# 02_CPU_1214C_DC_DC_DC.net
KiCad netlist of a schematic drawn in Altium Designer
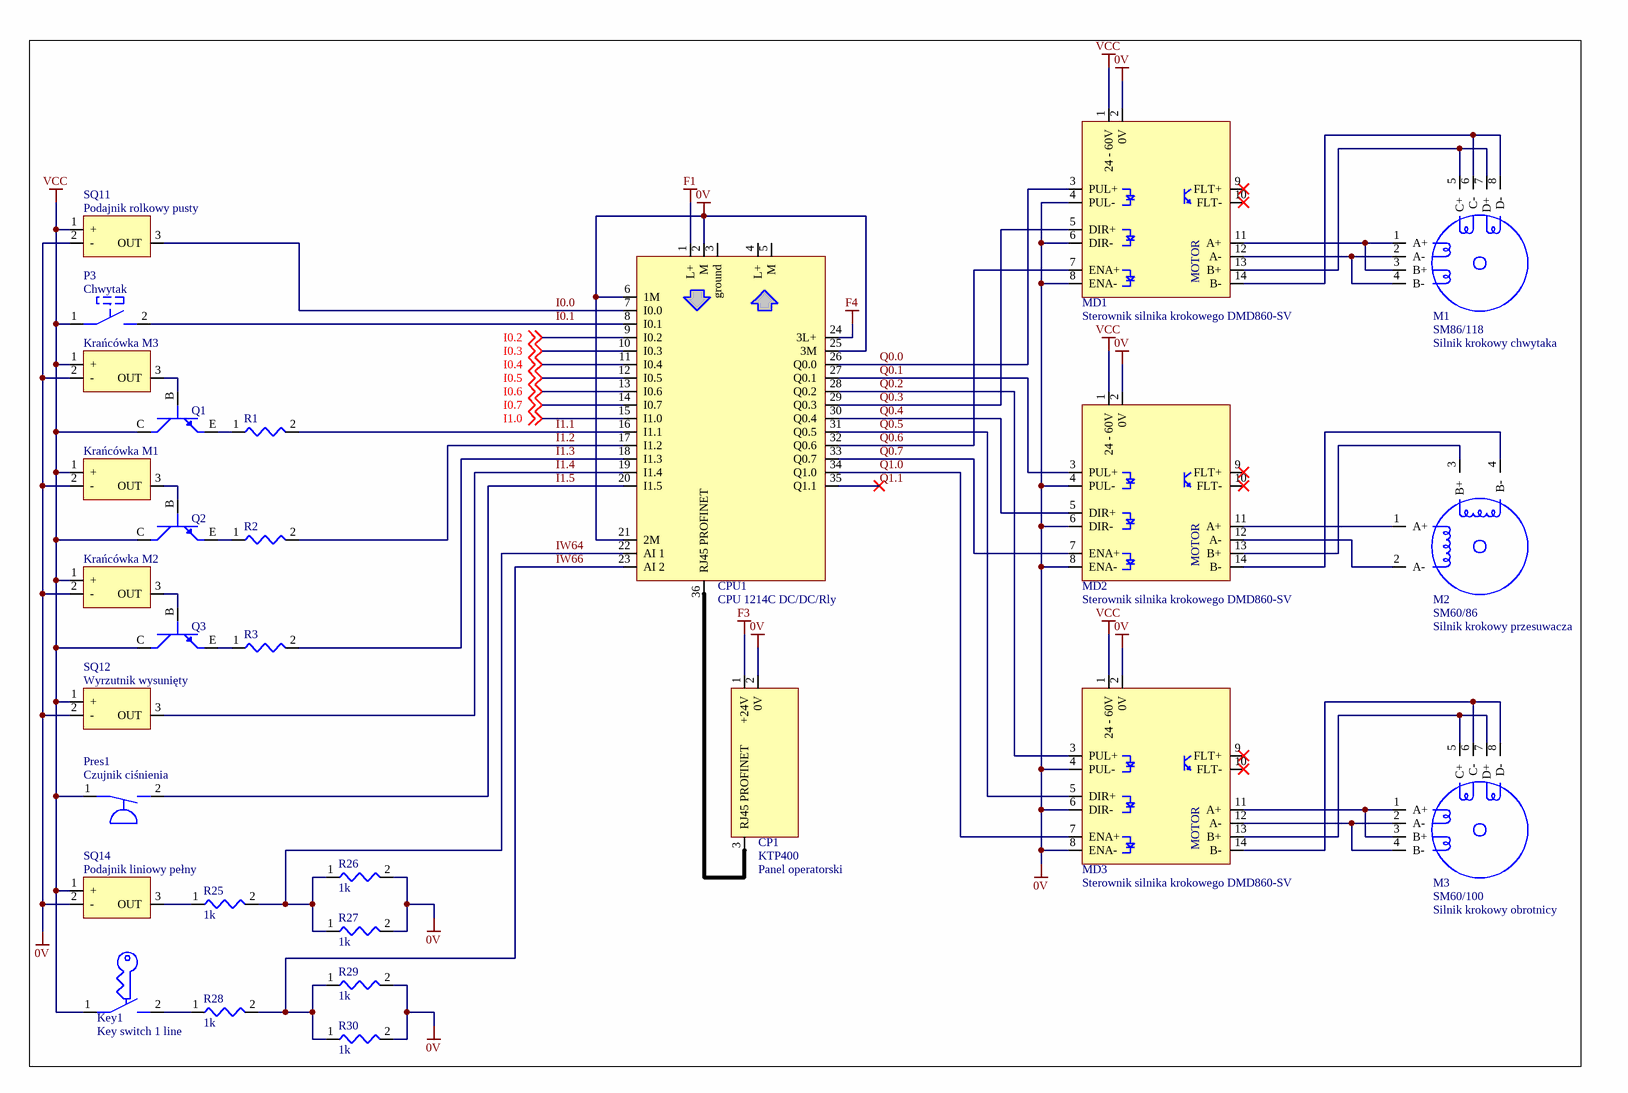
[diagram p0: [02] CPU 1214C DC_DC_DC.SchDoc]

(export (version "E")
  (design (tool "Eeschema 10.0.6"))
  (components
    (comp (ref "CP1") (value "KTP400") (libsource (lib "Schlib1") (part "KTP 400 Basic")))
    (comp (ref "CPU1") (value "CPU 1214C DC/DC/Rly") (libsource (lib "Schlib1") (part "CPU 1214C DC/DC/DC")))
    (comp (ref "Key1") (value "Key switch 1 line") (libsource (lib "Schlib1") (part "Key switch 1 line")))
    (comp (ref "LM1") (value "Krańcówka M1") (libsource (lib "Schlib1") (part "Sensor PNP")))
    (comp (ref "LM2") (value "Krańcówka M2") (libsource (lib "Schlib1") (part "Sensor PNP")))
    (comp (ref "LM3") (value "Krańcówka M3") (libsource (lib "Schlib1") (part "Sensor PNP")))
    (comp (ref "M1") (value "SM86/118") (libsource (lib "Schlib1") (part "Stepper motor 8-wire small")))
    (comp (ref "M2") (value "SM60/86") (libsource (lib "Schlib1") (part "Stepper motor 4-wire small")))
    (comp (ref "M3") (value "SM60/100") (libsource (lib "Schlib1") (part "Stepper motor 8-wire small")))
    (comp (ref "MD1")
      (value "Sterownik silnika krokowego DMD860-SV")
      (libsource (lib "Schlib1") (part "Stepper motor driver DMD860-SV"))
    )
    (comp (ref "MD2")
      (value "Sterownik silnika krokowego DMD860-SV")
      (libsource (lib "Schlib1") (part "Stepper motor driver DMD860-SV"))
    )
    (comp (ref "MD3")
      (value "Sterownik silnika krokowego DMD860-SV")
      (libsource (lib "Schlib1") (part "Stepper motor driver DMD860-SV"))
    )
    (comp (ref "P3") (value "Chwytak") (libsource (lib "Schlib1") (part "Button NO")))
    (comp (ref "Pres1") (value "Czujnik ciśnienia") (libsource (lib "Schlib1") (part "Pressostat NO")))
    (comp (ref "Q1") (value "NPN") (libsource (lib "Schlib1") (part "NPN Transistor")))
    (comp (ref "Q2") (value "NPN") (libsource (lib "Schlib1") (part "NPN Transistor")))
    (comp (ref "Q3") (value "NPN") (libsource (lib "Schlib1") (part "NPN Transistor")))
    (comp (ref "R1") (value "?R?") (libsource (lib "Schlib1") (part "Resistor")))
    (comp (ref "R2") (value "?R?") (libsource (lib "Schlib1") (part "Resistor")))
    (comp (ref "R3") (value "?R?") (libsource (lib "Schlib1") (part "Resistor")))
    (comp (ref "R25") (value "1k") (libsource (lib "Schlib1") (part "Resistor")))
    (comp (ref "R26") (value "1k") (libsource (lib "Schlib1") (part "Resistor")))
    (comp (ref "R27") (value "1k") (libsource (lib "Schlib1") (part "Resistor")))
    (comp (ref "R28") (value "1k") (libsource (lib "Schlib1") (part "Resistor")))
    (comp (ref "R29") (value "1k") (libsource (lib "Schlib1") (part "Resistor")))
    (comp (ref "R30") (value "1k") (libsource (lib "Schlib1") (part "Resistor")))
    (comp (ref "SQ11") (value "Podajnik rolkowy pusty") (libsource (lib "Schlib1") (part "Sensor PNP")))
    (comp (ref "SQ12") (value "Wyrzutnik wysunięty") (libsource (lib "Schlib1") (part "Sensor PNP")))
    (comp (ref "SQ14") (value "Podajnik liniowy pełny") (libsource (lib "Schlib1") (part "Sensor PNP")))
  )
  (nets
    (net (code "1") (name "/I0.0") (class "Default")
      (node (ref "CPU1") (pin "7") (pinfunction "I0.0_7") (pintype "passive"))
      (node (ref "SQ11") (pin "3") (pinfunction "OUT_3") (pintype "passive"))
    )
    (net (code "2") (name "/I0.1") (class "Default")
      (node (ref "CPU1") (pin "8") (pinfunction "I0.1_8") (pintype "passive"))
      (node (ref "P3") (pin "2") (pinfunction "*_2") (pintype "passive"))
    )
    (net (code "3") (name "/I1.1") (class "Default")
      (node (ref "CPU1") (pin "16") (pinfunction "I1.1_16") (pintype "passive"))
      (node (ref "R1") (pin "2") (pinfunction "4_2") (pintype "passive"))
    )
    (net (code "4") (name "/I1.2") (class "Default")
      (node (ref "CPU1") (pin "17") (pinfunction "I1.2_17") (pintype "passive"))
      (node (ref "R2") (pin "2") (pinfunction "4_2") (pintype "passive"))
    )
    (net (code "5") (name "/I1.3") (class "Default")
      (node (ref "CPU1") (pin "18") (pinfunction "I1.3_18") (pintype "passive"))
      (node (ref "R3") (pin "2") (pinfunction "4_2") (pintype "passive"))
    )
    (net (code "6") (name "/I1.4") (class "Default")
      (node (ref "CPU1") (pin "19") (pinfunction "I1.4_19") (pintype "passive"))
      (node (ref "SQ12") (pin "3") (pinfunction "OUT_3") (pintype "passive"))
    )
    (net (code "7") (name "/I1.5") (class "Default")
      (node (ref "CPU1") (pin "20") (pinfunction "I1.5_20") (pintype "passive"))
      (node (ref "Pres1") (pin "2") (pinfunction "2_2") (pintype "passive"))
    )
    (net (code "8") (name "/IW64") (class "Default")
      (node (ref "CPU1") (pin "22") (pinfunction "AI_1_22") (pintype "passive"))
      (node (ref "R25") (pin "2") (pinfunction "4_2") (pintype "passive"))
      (node (ref "R26") (pin "1") (pinfunction "3_1") (pintype "passive"))
      (node (ref "R27") (pin "1") (pinfunction "3_1") (pintype "passive"))
    )
    (net (code "9") (name "/IW66") (class "Default")
      (node (ref "CPU1") (pin "23") (pinfunction "AI_2_23") (pintype "passive"))
      (node (ref "R28") (pin "2") (pinfunction "4_2") (pintype "passive"))
      (node (ref "R29") (pin "1") (pinfunction "3_1") (pintype "passive"))
      (node (ref "R30") (pin "1") (pinfunction "3_1") (pintype "passive"))
    )
    (net (code "10") (name "/Q0.0") (class "Default")
      (node (ref "CPU1") (pin "26") (pinfunction "Q0.0_26") (pintype "passive"))
      (node (ref "MD1") (pin "3") (pinfunction "PUL+_3") (pintype "passive"))
    )
    (net (code "11") (name "/Q0.1") (class "Default")
      (node (ref "CPU1") (pin "27") (pinfunction "Q0.1_27") (pintype "passive"))
      (node (ref "MD2") (pin "3") (pinfunction "PUL+_3") (pintype "passive"))
    )
    (net (code "12") (name "/Q0.2") (class "Default")
      (node (ref "CPU1") (pin "28") (pinfunction "Q0.2_28") (pintype "passive"))
      (node (ref "MD3") (pin "3") (pinfunction "PUL+_3") (pintype "passive"))
    )
    (net (code "13") (name "/Q0.3") (class "Default")
      (node (ref "CPU1") (pin "29") (pinfunction "Q0.3_29") (pintype "passive"))
      (node (ref "MD1") (pin "5") (pinfunction "DIR+_5") (pintype "passive"))
    )
    (net (code "14") (name "/Q0.4") (class "Default")
      (node (ref "CPU1") (pin "30") (pinfunction "Q0.4_30") (pintype "passive"))
      (node (ref "MD2") (pin "5") (pinfunction "DIR+_5") (pintype "passive"))
    )
    (net (code "15") (name "/Q0.5") (class "Default")
      (node (ref "CPU1") (pin "31") (pinfunction "Q0.5_31") (pintype "passive"))
      (node (ref "MD3") (pin "5") (pinfunction "DIR+_5") (pintype "passive"))
    )
    (net (code "16") (name "/Q0.6") (class "Default")
      (node (ref "CPU1") (pin "32") (pinfunction "Q0.6_32") (pintype "passive"))
      (node (ref "MD1") (pin "7") (pinfunction "ENA+_7") (pintype "passive"))
    )
    (net (code "17") (name "/Q0.7") (class "Default")
      (node (ref "CPU1") (pin "33") (pinfunction "Q0.7_33") (pintype "passive"))
      (node (ref "MD2") (pin "7") (pinfunction "ENA+_7") (pintype "passive"))
    )
    (net (code "18") (name "/Q1.0") (class "Default")
      (node (ref "CPU1") (pin "34") (pinfunction "Q1.0_34") (pintype "passive"))
      (node (ref "MD3") (pin "7") (pinfunction "ENA+_7") (pintype "passive"))
    )
    (net (code "19") (name "/Q1.1") (class "Default")
      (node (ref "CPU1") (pin "35") (pinfunction "Q1.1_35") (pintype "passive+no_connect"))
    )
    (net (code "20") (name "0V") (class "Default")
      (node (ref "CP1") (pin "2") (pinfunction "0V_2") (pintype "passive"))
      (node (ref "CPU1") (pin "2") (pinfunction "M_2") (pintype "passive"))
      (node (ref "CPU1") (pin "21") (pinfunction "2M_21") (pintype "passive"))
      (node (ref "CPU1") (pin "25") (pinfunction "3M_25") (pintype "passive"))
      (node (ref "CPU1") (pin "6") (pinfunction "1M_6") (pintype "passive"))
      (node (ref "LM1") (pin "2") (pinfunction "-_2") (pintype "passive"))
      (node (ref "LM2") (pin "2") (pinfunction "-_2") (pintype "passive"))
      (node (ref "LM3") (pin "2") (pinfunction "-_2") (pintype "passive"))
      (node (ref "MD1") (pin "2") (pinfunction "0V_2") (pintype "passive"))
      (node (ref "MD1") (pin "4") (pinfunction "PUL-_4") (pintype "passive"))
      (node (ref "MD1") (pin "6") (pinfunction "DIR-_6") (pintype "passive"))
      (node (ref "MD1") (pin "8") (pinfunction "ENA-_8") (pintype "passive"))
      (node (ref "MD2") (pin "2") (pinfunction "0V_2") (pintype "passive"))
      (node (ref "MD2") (pin "4") (pinfunction "PUL-_4") (pintype "passive"))
      (node (ref "MD2") (pin "6") (pinfunction "DIR-_6") (pintype "passive"))
      (node (ref "MD2") (pin "8") (pinfunction "ENA-_8") (pintype "passive"))
      (node (ref "MD3") (pin "2") (pinfunction "0V_2") (pintype "passive"))
      (node (ref "MD3") (pin "4") (pinfunction "PUL-_4") (pintype "passive"))
      (node (ref "MD3") (pin "6") (pinfunction "DIR-_6") (pintype "passive"))
      (node (ref "MD3") (pin "8") (pinfunction "ENA-_8") (pintype "passive"))
      (node (ref "R26") (pin "2") (pinfunction "4_2") (pintype "passive"))
      (node (ref "R27") (pin "2") (pinfunction "4_2") (pintype "passive"))
      (node (ref "R29") (pin "2") (pinfunction "4_2") (pintype "passive"))
      (node (ref "R30") (pin "2") (pinfunction "4_2") (pintype "passive"))
      (node (ref "SQ11") (pin "2") (pinfunction "-_2") (pintype "passive"))
      (node (ref "SQ12") (pin "2") (pinfunction "-_2") (pintype "passive"))
      (node (ref "SQ14") (pin "2") (pinfunction "-_2") (pintype "passive"))
    )
    (net (code "21") (name "F1") (class "Default")
      (node (ref "CPU1") (pin "1") (pinfunction "L+_1") (pintype "passive"))
    )
    (net (code "22") (name "F3") (class "Default")
      (node (ref "CP1") (pin "1") (pinfunction "+24V_1") (pintype "passive"))
    )
    (net (code "23") (name "F4") (class "Default")
      (node (ref "CPU1") (pin "24") (pinfunction "3L+_24") (pintype "passive"))
    )
    (net (code "24") (name "I0.2") (class "Default")
      (node (ref "CPU1") (pin "9") (pinfunction "I0.2_9") (pintype "passive"))
    )
    (net (code "25") (name "I0.3") (class "Default")
      (node (ref "CPU1") (pin "10") (pinfunction "I0.3_10") (pintype "passive"))
    )
    (net (code "26") (name "I0.4") (class "Default")
      (node (ref "CPU1") (pin "11") (pinfunction "I0.4_11") (pintype "passive"))
    )
    (net (code "27") (name "I0.5") (class "Default")
      (node (ref "CPU1") (pin "12") (pinfunction "I0.5_12") (pintype "passive"))
    )
    (net (code "28") (name "I0.6") (class "Default")
      (node (ref "CPU1") (pin "13") (pinfunction "I0.6_13") (pintype "passive"))
    )
    (net (code "29") (name "I0.7") (class "Default")
      (node (ref "CPU1") (pin "14") (pinfunction "I0.7_14") (pintype "passive"))
    )
    (net (code "30") (name "I1.0") (class "Default")
      (node (ref "CPU1") (pin "15") (pinfunction "I1.0_15") (pintype "passive"))
    )
    (net (code "31") (name "Net-(CP1-RJ45_PROFINET)") (class "Default")
      (node (ref "CP1") (pin "3") (pinfunction "RJ45_PROFINET_3") (pintype "passive"))
      (node (ref "CPU1") (pin "36") (pinfunction "RJ45_PROFINET_36") (pintype "passive"))
    )
    (net (code "32") (name "Net-(LM1-OUT)") (class "Default")
      (node (ref "LM1") (pin "3") (pinfunction "OUT_3") (pintype "passive"))
      (node (ref "Q2") (pin "B") (pinfunction "B_B") (pintype "passive"))
    )
    (net (code "33") (name "Net-(LM2-OUT)") (class "Default")
      (node (ref "LM2") (pin "3") (pinfunction "OUT_3") (pintype "passive"))
      (node (ref "Q3") (pin "B") (pinfunction "B_B") (pintype "passive"))
    )
    (net (code "34") (name "Net-(LM3-OUT)") (class "Default")
      (node (ref "LM3") (pin "3") (pinfunction "OUT_3") (pintype "passive"))
      (node (ref "Q1") (pin "B") (pinfunction "B_B") (pintype "passive"))
    )
    (net (code "35") (name "Net-(M1-A+)") (class "Default")
      (node (ref "M1") (pin "1") (pinfunction "A+_1") (pintype "passive"))
      (node (ref "M1") (pin "3") (pinfunction "B+_3") (pintype "passive"))
      (node (ref "MD1") (pin "11") (pinfunction "A+_11") (pintype "passive"))
    )
    (net (code "36") (name "Net-(M1-A-)") (class "Default")
      (node (ref "M1") (pin "2") (pinfunction "A-_2") (pintype "passive"))
      (node (ref "M1") (pin "4") (pinfunction "B-_4") (pintype "passive"))
      (node (ref "MD1") (pin "12") (pinfunction "A-_12") (pintype "passive"))
    )
    (net (code "37") (name "Net-(M1-C+)") (class "Default")
      (node (ref "M1") (pin "5") (pinfunction "C+_5") (pintype "passive"))
      (node (ref "M1") (pin "7") (pinfunction "D+_7") (pintype "passive"))
      (node (ref "MD1") (pin "13") (pinfunction "B+_13") (pintype "passive"))
    )
    (net (code "38") (name "Net-(M1-C-)") (class "Default")
      (node (ref "M1") (pin "6") (pinfunction "C-_6") (pintype "passive"))
      (node (ref "M1") (pin "8") (pinfunction "D-_8") (pintype "passive"))
      (node (ref "MD1") (pin "14") (pinfunction "B-_14") (pintype "passive"))
    )
    (net (code "39") (name "Net-(M2-A+)") (class "Default")
      (node (ref "M2") (pin "1") (pinfunction "A+_1") (pintype "passive"))
      (node (ref "MD2") (pin "11") (pinfunction "A+_11") (pintype "passive"))
    )
    (net (code "40") (name "Net-(M2-A-)") (class "Default")
      (node (ref "M2") (pin "2") (pinfunction "A-_2") (pintype "passive"))
      (node (ref "MD2") (pin "12") (pinfunction "A-_12") (pintype "passive"))
    )
    (net (code "41") (name "Net-(M2-B+)") (class "Default")
      (node (ref "M2") (pin "3") (pinfunction "B+_3") (pintype "passive"))
      (node (ref "MD2") (pin "13") (pinfunction "B+_13") (pintype "passive"))
    )
    (net (code "42") (name "Net-(M2-B-)") (class "Default")
      (node (ref "M2") (pin "4") (pinfunction "B-_4") (pintype "passive"))
      (node (ref "MD2") (pin "14") (pinfunction "B-_14") (pintype "passive"))
    )
    (net (code "43") (name "Net-(M3-A+)") (class "Default")
      (node (ref "M3") (pin "1") (pinfunction "A+_1") (pintype "passive"))
      (node (ref "M3") (pin "3") (pinfunction "B+_3") (pintype "passive"))
      (node (ref "MD3") (pin "11") (pinfunction "A+_11") (pintype "passive"))
    )
    (net (code "44") (name "Net-(M3-A-)") (class "Default")
      (node (ref "M3") (pin "2") (pinfunction "A-_2") (pintype "passive"))
      (node (ref "M3") (pin "4") (pinfunction "B-_4") (pintype "passive"))
      (node (ref "MD3") (pin "12") (pinfunction "A-_12") (pintype "passive"))
    )
    (net (code "45") (name "Net-(M3-C+)") (class "Default")
      (node (ref "M3") (pin "5") (pinfunction "C+_5") (pintype "passive"))
      (node (ref "M3") (pin "7") (pinfunction "D+_7") (pintype "passive"))
      (node (ref "MD3") (pin "13") (pinfunction "B+_13") (pintype "passive"))
    )
    (net (code "46") (name "Net-(M3-C-)") (class "Default")
      (node (ref "M3") (pin "6") (pinfunction "C-_6") (pintype "passive"))
      (node (ref "M3") (pin "8") (pinfunction "D-_8") (pintype "passive"))
      (node (ref "MD3") (pin "14") (pinfunction "B-_14") (pintype "passive"))
    )
    (net (code "47") (name "Net-(R1-3)") (class "Default")
      (node (ref "Q1") (pin "E") (pinfunction "E_E") (pintype "passive"))
      (node (ref "R1") (pin "1") (pinfunction "3_1") (pintype "passive"))
    )
    (net (code "48") (name "Net-(R2-3)") (class "Default")
      (node (ref "Q2") (pin "E") (pinfunction "E_E") (pintype "passive"))
      (node (ref "R2") (pin "1") (pinfunction "3_1") (pintype "passive"))
    )
    (net (code "49") (name "Net-(R3-3)") (class "Default")
      (node (ref "Q3") (pin "E") (pinfunction "E_E") (pintype "passive"))
      (node (ref "R3") (pin "1") (pinfunction "3_1") (pintype "passive"))
    )
    (net (code "50") (name "Net-(R25-3)") (class "Default")
      (node (ref "R25") (pin "1") (pinfunction "3_1") (pintype "passive"))
      (node (ref "SQ14") (pin "3") (pinfunction "OUT_3") (pintype "passive"))
    )
    (net (code "51") (name "Net-(R28-3)") (class "Default")
      (node (ref "Key1") (pin "2") (pinfunction "*_2") (pintype "passive"))
      (node (ref "R28") (pin "1") (pinfunction "3_1") (pintype "passive"))
    )
    (net (code "52") (name "VCC") (class "Default")
      (node (ref "Key1") (pin "1") (pinfunction "*_1") (pintype "passive"))
      (node (ref "LM1") (pin "1") (pinfunction "+_1") (pintype "passive"))
      (node (ref "LM2") (pin "1") (pinfunction "+_1") (pintype "passive"))
      (node (ref "LM3") (pin "1") (pinfunction "+_1") (pintype "passive"))
      (node (ref "MD1") (pin "1") (pinfunction "24_-_60V_1") (pintype "passive"))
      (node (ref "MD2") (pin "1") (pinfunction "24_-_60V_1") (pintype "passive"))
      (node (ref "MD3") (pin "1") (pinfunction "24_-_60V_1") (pintype "passive"))
      (node (ref "P3") (pin "1") (pinfunction "*_1") (pintype "passive"))
      (node (ref "Pres1") (pin "1") (pinfunction "1_1") (pintype "passive"))
      (node (ref "Q1") (pin "C") (pinfunction "C_C") (pintype "passive"))
      (node (ref "Q2") (pin "C") (pinfunction "C_C") (pintype "passive"))
      (node (ref "Q3") (pin "C") (pinfunction "C_C") (pintype "passive"))
      (node (ref "SQ11") (pin "1") (pinfunction "+_1") (pintype "passive"))
      (node (ref "SQ12") (pin "1") (pinfunction "+_1") (pintype "passive"))
      (node (ref "SQ14") (pin "1") (pinfunction "+_1") (pintype "passive"))
    )
    (net (code "53") (name "unconnected-(CPU1-L+-Pad4)") (class "Default")
      (node (ref "CPU1") (pin "4") (pinfunction "L+_4") (pintype "passive"))
    )
    (net (code "54") (name "unconnected-(CPU1-M-Pad5)") (class "Default")
      (node (ref "CPU1") (pin "5") (pinfunction "M_5") (pintype "passive"))
    )
    (net (code "55") (name "unconnected-(CPU1-ground-Pad3)") (class "Default")
      (node (ref "CPU1") (pin "3") (pinfunction "ground_3") (pintype "passive"))
    )
    (net (code "56") (name "unconnected-(MD1-FLT+-Pad9)") (class "Default")
      (node (ref "MD1") (pin "9") (pinfunction "FLT+_9") (pintype "passive+no_connect"))
    )
    (net (code "57") (name "unconnected-(MD1-FLT--Pad10)") (class "Default")
      (node (ref "MD1") (pin "10") (pinfunction "FLT-_10") (pintype "passive+no_connect"))
    )
    (net (code "58") (name "unconnected-(MD2-FLT+-Pad9)") (class "Default")
      (node (ref "MD2") (pin "9") (pinfunction "FLT+_9") (pintype "passive+no_connect"))
    )
    (net (code "59") (name "unconnected-(MD2-FLT--Pad10)") (class "Default")
      (node (ref "MD2") (pin "10") (pinfunction "FLT-_10") (pintype "passive+no_connect"))
    )
    (net (code "60") (name "unconnected-(MD3-FLT+-Pad9)") (class "Default")
      (node (ref "MD3") (pin "9") (pinfunction "FLT+_9") (pintype "passive+no_connect"))
    )
    (net (code "61") (name "unconnected-(MD3-FLT--Pad10)") (class "Default")
      (node (ref "MD3") (pin "10") (pinfunction "FLT-_10") (pintype "passive+no_connect"))
    )
  )
)
